# Keyboard_V2.net
KiCad netlist of a schematic drawn in EasyEDA
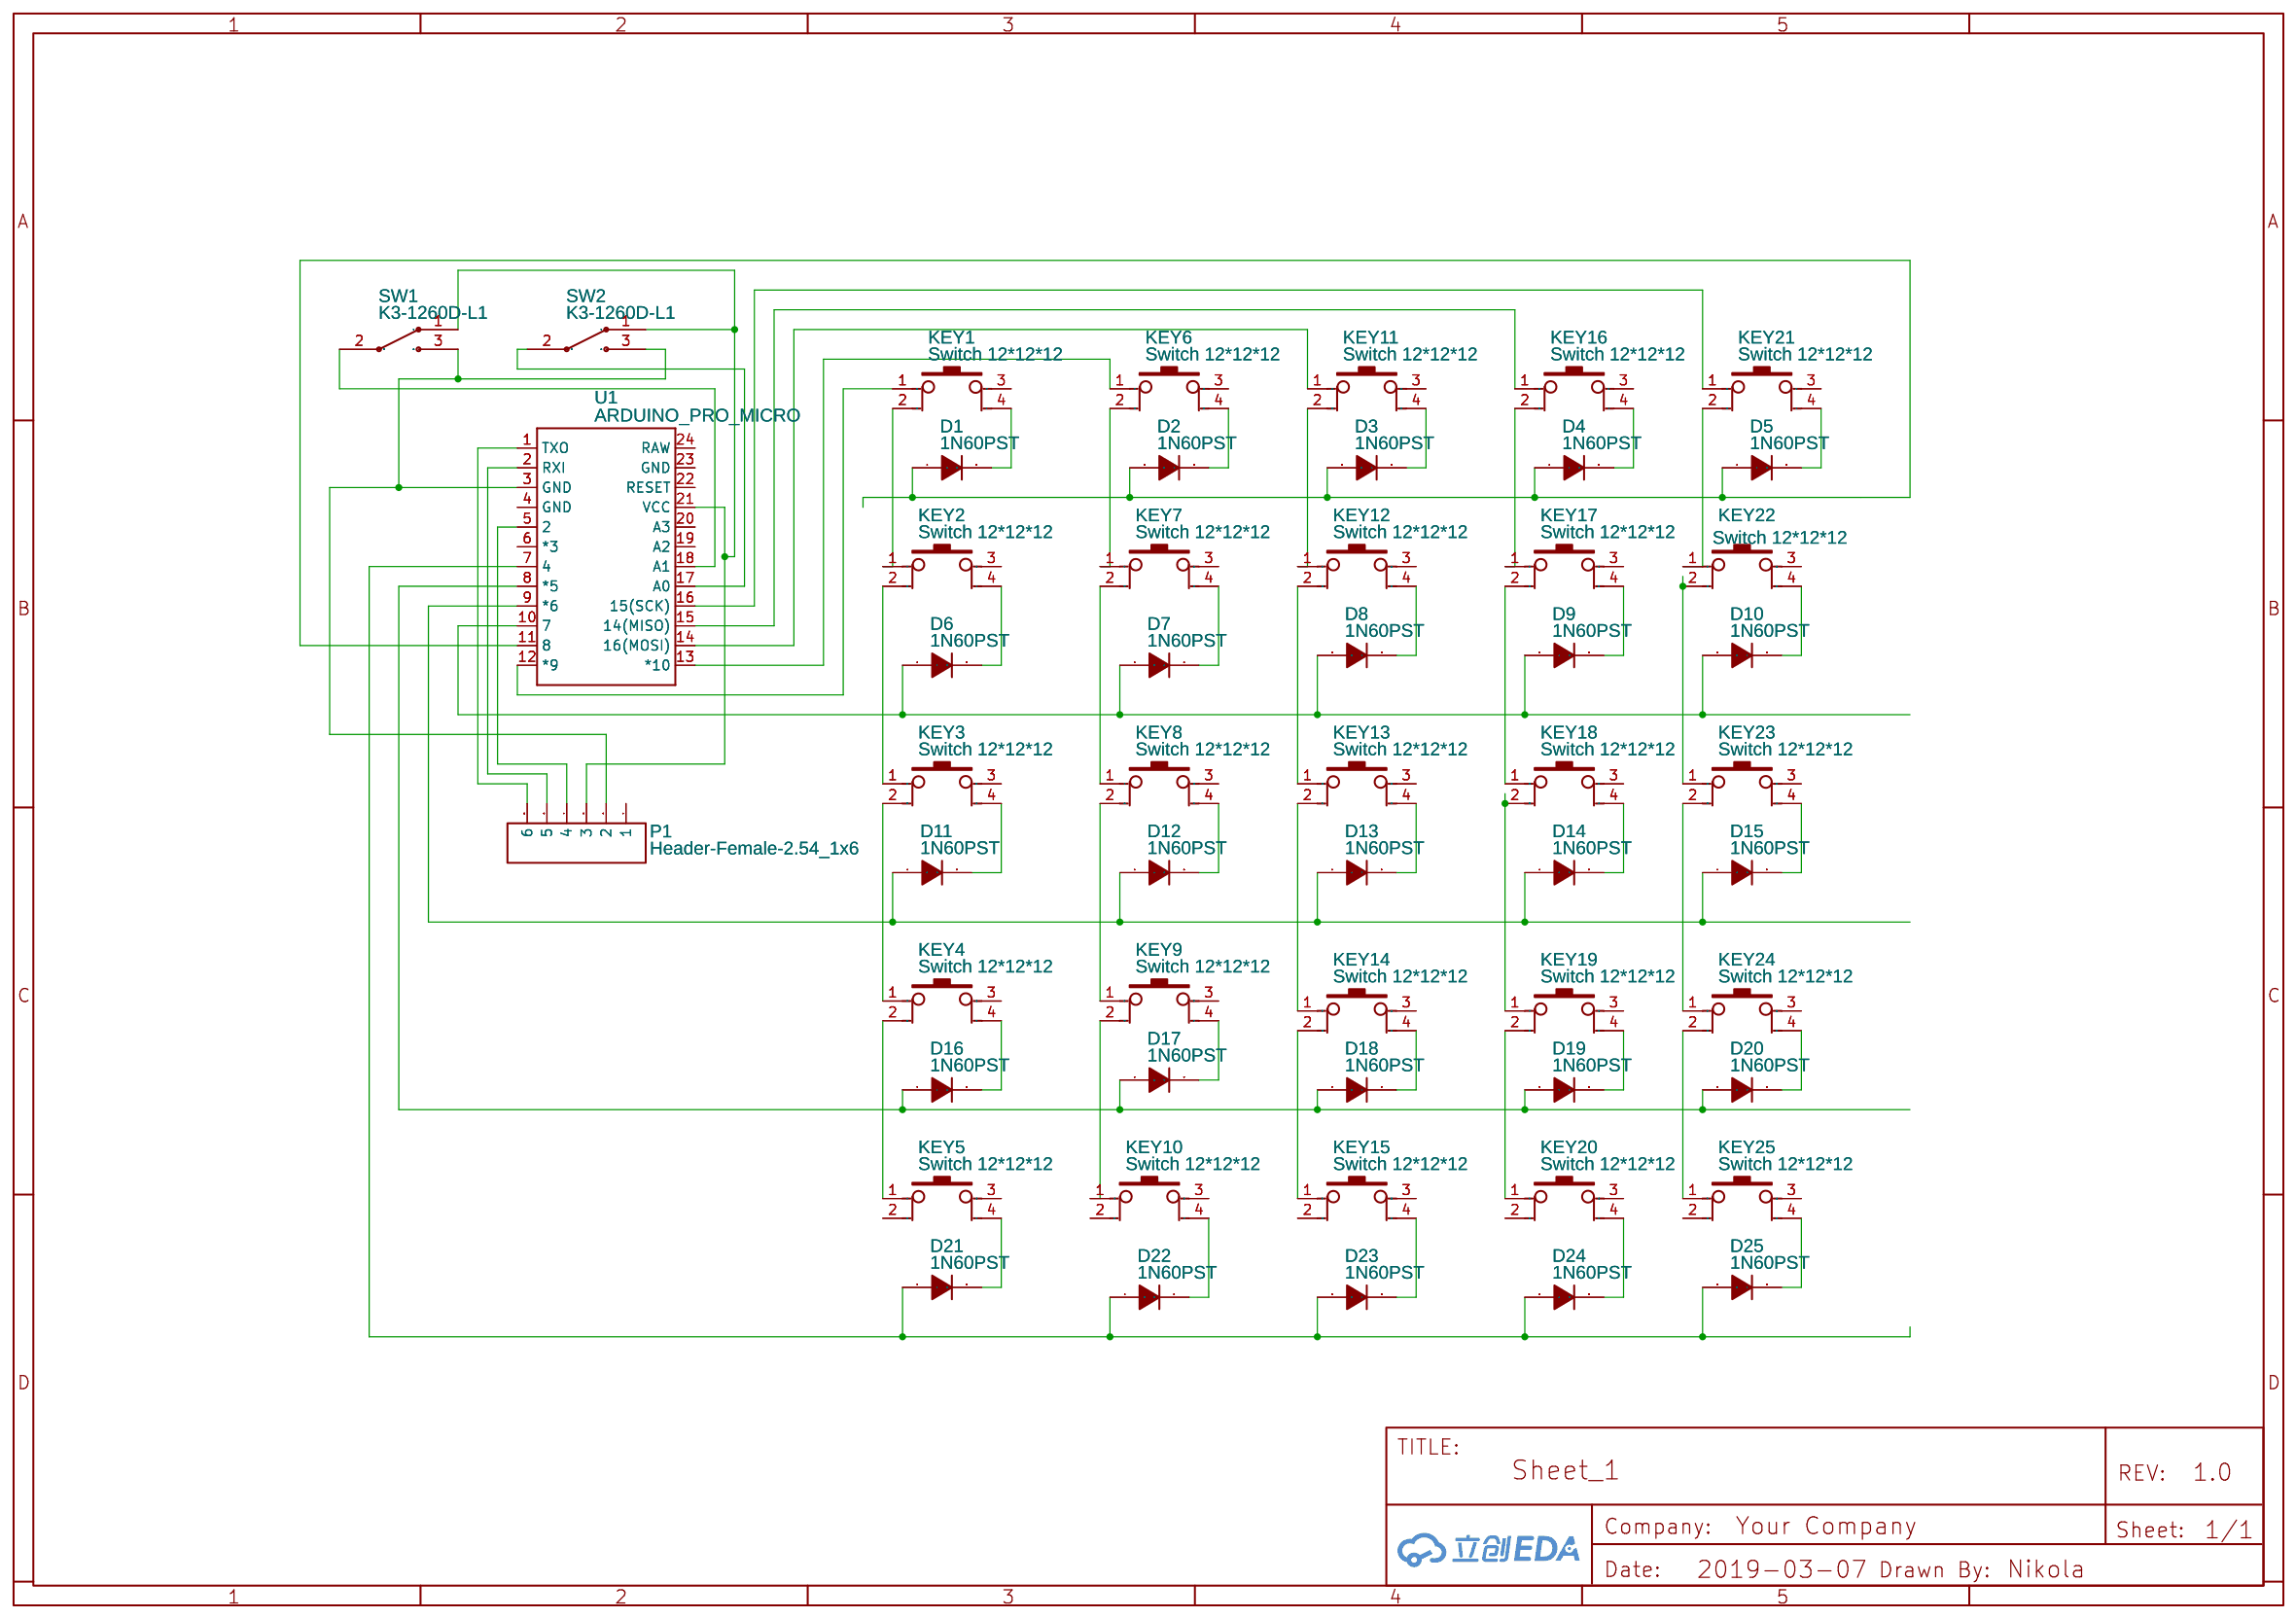
[diagram p0: schematic sheet]

(export (version "E")
  (design (tool "Eeschema 10.0.6"))
  (components
    (comp (ref "D1")
      (value "1N60PST")
      (fields (field (name "BOM_Supplier Part") "C41623"))
      (libsource (lib "") (part "Unknown_475_230"))
    )
    (comp (ref "D2")
      (value "1N60PST")
      (fields (field (name "BOM_Supplier Part") "C41623"))
      (libsource (lib "") (part "Unknown_585_230"))
    )
    (comp (ref "D3")
      (value "1N60PST")
      (fields (field (name "BOM_Supplier Part") "C41623"))
      (libsource (lib "") (part "Unknown_685_230"))
    )
    (comp (ref "D4")
      (value "1N60PST")
      (fields (field (name "BOM_Supplier Part") "C41623"))
      (libsource (lib "") (part "Unknown_790_230"))
    )
    (comp (ref "D5")
      (value "1N60PST")
      (fields (field (name "BOM_Supplier Part") "C41623"))
      (libsource (lib "") (part "Unknown_885_230"))
    )
    (comp (ref "D6")
      (value "1N60PST")
      (fields (field (name "BOM_Supplier Part") "C41623"))
      (libsource (lib "") (part "Unknown_470_330"))
    )
    (comp (ref "D7")
      (value "1N60PST")
      (fields (field (name "BOM_Supplier Part") "C41623"))
      (libsource (lib "") (part "Unknown_580_330"))
    )
    (comp (ref "D8")
      (value "1N60PST")
      (fields (field (name "BOM_Supplier Part") "C41623"))
      (libsource (lib "") (part "Unknown_680_325"))
    )
    (comp (ref "D9")
      (value "1N60PST")
      (fields (field (name "BOM_Supplier Part") "C41623"))
      (libsource (lib "") (part "Unknown_785_325"))
    )
    (comp (ref "D10")
      (value "1N60PST")
      (fields (field (name "BOM_Supplier Part") "C41623"))
      (libsource (lib "") (part "Unknown_875_325"))
    )
    (comp (ref "D11")
      (value "1N60PST")
      (fields (field (name "BOM_Supplier Part") "C41623"))
      (libsource (lib "") (part "Unknown_465_435"))
    )
    (comp (ref "D12")
      (value "1N60PST")
      (fields (field (name "BOM_Supplier Part") "C41623"))
      (libsource (lib "") (part "Unknown_580_435"))
    )
    (comp (ref "D13")
      (value "1N60PST")
      (fields (field (name "BOM_Supplier Part") "C41623"))
      (libsource (lib "") (part "Unknown_680_435"))
    )
    (comp (ref "D14")
      (value "1N60PST")
      (fields (field (name "BOM_Supplier Part") "C41623"))
      (libsource (lib "") (part "Unknown_785_435"))
    )
    (comp (ref "D15")
      (value "1N60PST")
      (fields (field (name "BOM_Supplier Part") "C41623"))
      (libsource (lib "") (part "Unknown_875_435"))
    )
    (comp (ref "D16")
      (value "1N60PST")
      (fields (field (name "BOM_Supplier Part") "C41623"))
      (libsource (lib "") (part "Unknown_470_545"))
    )
    (comp (ref "D17")
      (value "1N60PST")
      (fields (field (name "BOM_Supplier Part") "C41623"))
      (libsource (lib "") (part "Unknown_580_540"))
    )
    (comp (ref "D18")
      (value "1N60PST")
      (fields (field (name "BOM_Supplier Part") "C41623"))
      (libsource (lib "") (part "Unknown_680_545"))
    )
    (comp (ref "D19")
      (value "1N60PST")
      (fields (field (name "BOM_Supplier Part") "C41623"))
      (libsource (lib "") (part "Unknown_785_545"))
    )
    (comp (ref "D20")
      (value "1N60PST")
      (fields (field (name "BOM_Supplier Part") "C41623"))
      (libsource (lib "") (part "Unknown_875_545"))
    )
    (comp (ref "D21")
      (value "1N60PST")
      (fields (field (name "BOM_Supplier Part") "C41623"))
      (libsource (lib "") (part "Unknown_470_645"))
    )
    (comp (ref "D22")
      (value "1N60PST")
      (fields (field (name "BOM_Supplier Part") "C41623"))
      (libsource (lib "") (part "Unknown_575_650"))
    )
    (comp (ref "D23")
      (value "1N60PST")
      (fields (field (name "BOM_Supplier Part") "C41623"))
      (libsource (lib "") (part "Unknown_680_650"))
    )
    (comp (ref "D24")
      (value "1N60PST")
      (fields (field (name "BOM_Supplier Part") "C41623"))
      (libsource (lib "") (part "Unknown_785_650"))
    )
    (comp (ref "D25")
      (value "1N60PST")
      (fields (field (name "BOM_Supplier Part") "C41623"))
      (libsource (lib "") (part "Unknown_875_645"))
    )
    (comp (ref "KEY1")
      (value "Switch 12*12*12")
      (fields (field (name "BOM_Supplier Part") "C14121"))
      (libsource (lib "") (part "Unknown_475_190"))
    )
    (comp (ref "KEY2")
      (value "Switch 12*12*12")
      (fields (field (name "BOM_Supplier Part") "C14121"))
      (libsource (lib "") (part "Unknown_470_280"))
    )
    (comp (ref "KEY3")
      (value "Switch 12*12*12")
      (fields (field (name "BOM_Supplier Part") "C14121"))
      (libsource (lib "") (part "Unknown_470_390"))
    )
    (comp (ref "KEY4")
      (value "Switch 12*12*12")
      (fields (field (name "BOM_Supplier Part") "C14121"))
      (libsource (lib "") (part "Unknown_470_500"))
    )
    (comp (ref "KEY5")
      (value "Switch 12*12*12")
      (fields (field (name "BOM_Supplier Part") "C14121"))
      (libsource (lib "") (part "Unknown_470_600"))
    )
    (comp (ref "KEY6")
      (value "Switch 12*12*12")
      (fields (field (name "BOM_Supplier Part") "C14121"))
      (libsource (lib "") (part "Unknown_585_190"))
    )
    (comp (ref "KEY7")
      (value "Switch 12*12*12")
      (fields (field (name "BOM_Supplier Part") "C14121"))
      (libsource (lib "") (part "Unknown_580_280"))
    )
    (comp (ref "KEY8")
      (value "Switch 12*12*12")
      (fields (field (name "BOM_Supplier Part") "C14121"))
      (libsource (lib "") (part "Unknown_580_390"))
    )
    (comp (ref "KEY9")
      (value "Switch 12*12*12")
      (fields (field (name "BOM_Supplier Part") "C14121"))
      (libsource (lib "") (part "Unknown_580_500"))
    )
    (comp (ref "KEY10")
      (value "Switch 12*12*12")
      (fields (field (name "BOM_Supplier Part") "C14121"))
      (libsource (lib "") (part "Unknown_575_600"))
    )
    (comp (ref "KEY11")
      (value "Switch 12*12*12")
      (fields (field (name "BOM_Supplier Part") "C14121"))
      (libsource (lib "") (part "Unknown_685_190"))
    )
    (comp (ref "KEY12")
      (value "Switch 12*12*12")
      (fields (field (name "BOM_Supplier Part") "C14121"))
      (libsource (lib "") (part "Unknown_680_280"))
    )
    (comp (ref "KEY13")
      (value "Switch 12*12*12")
      (fields (field (name "BOM_Supplier Part") "C14121"))
      (libsource (lib "") (part "Unknown_680_390"))
    )
    (comp (ref "KEY14")
      (value "Switch 12*12*12")
      (fields (field (name "BOM_Supplier Part") "C14121"))
      (libsource (lib "") (part "Unknown_680_505"))
    )
    (comp (ref "KEY15")
      (value "Switch 12*12*12")
      (fields (field (name "BOM_Supplier Part") "C14121"))
      (libsource (lib "") (part "Unknown_680_600"))
    )
    (comp (ref "KEY16")
      (value "Switch 12*12*12")
      (fields (field (name "BOM_Supplier Part") "C14121"))
      (libsource (lib "") (part "Unknown_790_190"))
    )
    (comp (ref "KEY17")
      (value "Switch 12*12*12")
      (fields (field (name "BOM_Supplier Part") "C14121"))
      (libsource (lib "") (part "Unknown_785_280"))
    )
    (comp (ref "KEY18")
      (value "Switch 12*12*12")
      (fields (field (name "BOM_Supplier Part") "C14121"))
      (libsource (lib "") (part "Unknown_785_390"))
    )
    (comp (ref "KEY19")
      (value "Switch 12*12*12")
      (fields (field (name "BOM_Supplier Part") "C14121"))
      (libsource (lib "") (part "Unknown_785_505"))
    )
    (comp (ref "KEY20")
      (value "Switch 12*12*12")
      (fields (field (name "BOM_Supplier Part") "C14121"))
      (libsource (lib "") (part "Unknown_785_600"))
    )
    (comp (ref "KEY21")
      (value "Switch 12*12*12")
      (fields (field (name "BOM_Supplier Part") "C14121"))
      (libsource (lib "") (part "Unknown_885_190"))
    )
    (comp (ref "KEY22")
      (value "Switch 12*12*12")
      (fields (field (name "BOM_Supplier Part") "C14121"))
      (libsource (lib "") (part "Unknown_875_280"))
    )
    (comp (ref "KEY23")
      (value "Switch 12*12*12")
      (fields (field (name "BOM_Supplier Part") "C14121"))
      (libsource (lib "") (part "Unknown_875_390"))
    )
    (comp (ref "KEY24")
      (value "Switch 12*12*12")
      (fields (field (name "BOM_Supplier Part") "C14121"))
      (libsource (lib "") (part "Unknown_875_505"))
    )
    (comp (ref "KEY25")
      (value "Switch 12*12*12")
      (fields (field (name "BOM_Supplier Part") "C14121"))
      (libsource (lib "") (part "Unknown_875_600"))
    )
    (comp (ref "P1")
      (value "Header-Female-2.54_1x6")
      (fields
        (field (name "BOM_Manufacturer Part") "Female header 1*6p")
        (field (name "BOM_Supplier Part") "C40877")
      )
      (libsource (lib "") (part "Unknown_285_415"))
    )
    (comp (ref "SW1")
      (value "K3-1260D-L1")
      (fields (field (name "BOM_Supplier Part") "C92657"))
      (libsource (lib "") (part "Unknown_195_160"))
    )
    (comp (ref "SW2")
      (value "K3-1260D-L1")
      (fields (field (name "BOM_Supplier Part") "C92657"))
      (libsource (lib "") (part "Unknown_290_160"))
    )
    (comp (ref "U1")
      (value "ARDUINO_PRO_MICRO")
      (fields (field (name "BOM_Manufacturer Part") "?"))
      (libsource (lib "") (part "Unknown_300_275"))
    )
  )
  (nets
    (net (code "1") (name "Net-(D1-A)") (class "Default")
      (node (ref "D1") (pin "1") (pinfunction "A_1") (pintype "unspecified"))
      (node (ref "D2") (pin "1") (pinfunction "A_1") (pintype "unspecified"))
      (node (ref "D3") (pin "1") (pinfunction "A_1") (pintype "unspecified"))
      (node (ref "D4") (pin "1") (pinfunction "A_1") (pintype "unspecified"))
      (node (ref "D5") (pin "1") (pinfunction "A_1") (pintype "unspecified"))
      (node (ref "U1") (pin "11") (pinfunction "8_11") (pintype "unspecified"))
    )
    (net (code "2") (name "Net-(D1-K)") (class "Default")
      (node (ref "D1") (pin "2") (pinfunction "K_2") (pintype "unspecified"))
      (node (ref "KEY1") (pin "4") (pinfunction "4_4") (pintype "input"))
    )
    (net (code "3") (name "Net-(D2-K)") (class "Default")
      (node (ref "D2") (pin "2") (pinfunction "K_2") (pintype "unspecified"))
      (node (ref "KEY6") (pin "4") (pinfunction "4_4") (pintype "input"))
    )
    (net (code "4") (name "Net-(D3-K)") (class "Default")
      (node (ref "D3") (pin "2") (pinfunction "K_2") (pintype "unspecified"))
      (node (ref "KEY11") (pin "4") (pinfunction "4_4") (pintype "input"))
    )
    (net (code "5") (name "Net-(D4-K)") (class "Default")
      (node (ref "D4") (pin "2") (pinfunction "K_2") (pintype "unspecified"))
      (node (ref "KEY16") (pin "4") (pinfunction "4_4") (pintype "input"))
    )
    (net (code "6") (name "Net-(D5-K)") (class "Default")
      (node (ref "D5") (pin "2") (pinfunction "K_2") (pintype "unspecified"))
      (node (ref "KEY21") (pin "4") (pinfunction "4_4") (pintype "input"))
    )
    (net (code "7") (name "Net-(D6-K)") (class "Default")
      (node (ref "D6") (pin "2") (pinfunction "K_2") (pintype "unspecified"))
      (node (ref "KEY2") (pin "4") (pinfunction "4_4") (pintype "input"))
    )
    (net (code "8") (name "Net-(D7-K)") (class "Default")
      (node (ref "D7") (pin "2") (pinfunction "K_2") (pintype "unspecified"))
      (node (ref "KEY7") (pin "4") (pinfunction "4_4") (pintype "input"))
    )
    (net (code "9") (name "Net-(D8-K)") (class "Default")
      (node (ref "D8") (pin "2") (pinfunction "K_2") (pintype "unspecified"))
      (node (ref "KEY12") (pin "4") (pinfunction "4_4") (pintype "input"))
    )
    (net (code "10") (name "Net-(D9-K)") (class "Default")
      (node (ref "D9") (pin "2") (pinfunction "K_2") (pintype "unspecified"))
      (node (ref "KEY17") (pin "4") (pinfunction "4_4") (pintype "input"))
    )
    (net (code "11") (name "Net-(D10-A)") (class "Default")
      (node (ref "D10") (pin "1") (pinfunction "A_1") (pintype "unspecified"))
      (node (ref "D6") (pin "1") (pinfunction "A_1") (pintype "unspecified"))
      (node (ref "D7") (pin "1") (pinfunction "A_1") (pintype "unspecified"))
      (node (ref "D8") (pin "1") (pinfunction "A_1") (pintype "unspecified"))
      (node (ref "D9") (pin "1") (pinfunction "A_1") (pintype "unspecified"))
      (node (ref "U1") (pin "10") (pinfunction "7_10") (pintype "unspecified"))
    )
    (net (code "12") (name "Net-(D10-K)") (class "Default")
      (node (ref "D10") (pin "2") (pinfunction "K_2") (pintype "unspecified"))
      (node (ref "KEY22") (pin "4") (pinfunction "4_4") (pintype "input"))
    )
    (net (code "13") (name "Net-(D11-A)") (class "Default")
      (node (ref "D11") (pin "1") (pinfunction "A_1") (pintype "unspecified"))
      (node (ref "D12") (pin "1") (pinfunction "A_1") (pintype "unspecified"))
      (node (ref "D13") (pin "1") (pinfunction "A_1") (pintype "unspecified"))
      (node (ref "D14") (pin "1") (pinfunction "A_1") (pintype "unspecified"))
      (node (ref "D15") (pin "1") (pinfunction "A_1") (pintype "unspecified"))
      (node (ref "U1") (pin "9") (pinfunction "*6_9") (pintype "unspecified"))
    )
    (net (code "14") (name "Net-(D11-K)") (class "Default")
      (node (ref "D11") (pin "2") (pinfunction "K_2") (pintype "unspecified"))
      (node (ref "KEY3") (pin "4") (pinfunction "4_4") (pintype "input"))
    )
    (net (code "15") (name "Net-(D12-K)") (class "Default")
      (node (ref "D12") (pin "2") (pinfunction "K_2") (pintype "unspecified"))
      (node (ref "KEY8") (pin "4") (pinfunction "4_4") (pintype "input"))
    )
    (net (code "16") (name "Net-(D13-K)") (class "Default")
      (node (ref "D13") (pin "2") (pinfunction "K_2") (pintype "unspecified"))
      (node (ref "KEY13") (pin "4") (pinfunction "4_4") (pintype "input"))
    )
    (net (code "17") (name "Net-(D14-K)") (class "Default")
      (node (ref "D14") (pin "2") (pinfunction "K_2") (pintype "unspecified"))
      (node (ref "KEY18") (pin "4") (pinfunction "4_4") (pintype "input"))
    )
    (net (code "18") (name "Net-(D15-K)") (class "Default")
      (node (ref "D15") (pin "2") (pinfunction "K_2") (pintype "unspecified"))
      (node (ref "KEY23") (pin "4") (pinfunction "4_4") (pintype "input"))
    )
    (net (code "19") (name "Net-(D16-A)") (class "Default")
      (node (ref "D16") (pin "1") (pinfunction "A_1") (pintype "unspecified"))
      (node (ref "D17") (pin "1") (pinfunction "A_1") (pintype "unspecified"))
      (node (ref "D18") (pin "1") (pinfunction "A_1") (pintype "unspecified"))
      (node (ref "D19") (pin "1") (pinfunction "A_1") (pintype "unspecified"))
      (node (ref "D20") (pin "1") (pinfunction "A_1") (pintype "unspecified"))
      (node (ref "U1") (pin "8") (pinfunction "*5_8") (pintype "unspecified"))
    )
    (net (code "20") (name "Net-(D16-K)") (class "Default")
      (node (ref "D16") (pin "2") (pinfunction "K_2") (pintype "unspecified"))
      (node (ref "KEY4") (pin "4") (pinfunction "4_4") (pintype "input"))
    )
    (net (code "21") (name "Net-(D17-K)") (class "Default")
      (node (ref "D17") (pin "2") (pinfunction "K_2") (pintype "unspecified"))
      (node (ref "KEY9") (pin "4") (pinfunction "4_4") (pintype "input"))
    )
    (net (code "22") (name "Net-(D18-K)") (class "Default")
      (node (ref "D18") (pin "2") (pinfunction "K_2") (pintype "unspecified"))
      (node (ref "KEY14") (pin "4") (pinfunction "4_4") (pintype "input"))
    )
    (net (code "23") (name "Net-(D19-K)") (class "Default")
      (node (ref "D19") (pin "2") (pinfunction "K_2") (pintype "unspecified"))
      (node (ref "KEY19") (pin "4") (pinfunction "4_4") (pintype "input"))
    )
    (net (code "24") (name "Net-(D20-K)") (class "Default")
      (node (ref "D20") (pin "2") (pinfunction "K_2") (pintype "unspecified"))
      (node (ref "KEY24") (pin "4") (pinfunction "4_4") (pintype "input"))
    )
    (net (code "25") (name "Net-(D21-A)") (class "Default")
      (node (ref "D21") (pin "1") (pinfunction "A_1") (pintype "unspecified"))
      (node (ref "D22") (pin "1") (pinfunction "A_1") (pintype "unspecified"))
      (node (ref "D23") (pin "1") (pinfunction "A_1") (pintype "unspecified"))
      (node (ref "D24") (pin "1") (pinfunction "A_1") (pintype "unspecified"))
      (node (ref "D25") (pin "1") (pinfunction "A_1") (pintype "unspecified"))
      (node (ref "U1") (pin "7") (pinfunction "4_7") (pintype "unspecified"))
    )
    (net (code "26") (name "Net-(D21-K)") (class "Default")
      (node (ref "D21") (pin "2") (pinfunction "K_2") (pintype "unspecified"))
      (node (ref "KEY5") (pin "4") (pinfunction "4_4") (pintype "input"))
    )
    (net (code "27") (name "Net-(D22-K)") (class "Default")
      (node (ref "D22") (pin "2") (pinfunction "K_2") (pintype "unspecified"))
      (node (ref "KEY10") (pin "4") (pinfunction "4_4") (pintype "input"))
    )
    (net (code "28") (name "Net-(D23-K)") (class "Default")
      (node (ref "D23") (pin "2") (pinfunction "K_2") (pintype "unspecified"))
      (node (ref "KEY15") (pin "4") (pinfunction "4_4") (pintype "input"))
    )
    (net (code "29") (name "Net-(D24-K)") (class "Default")
      (node (ref "D24") (pin "2") (pinfunction "K_2") (pintype "unspecified"))
      (node (ref "KEY20") (pin "4") (pinfunction "4_4") (pintype "input"))
    )
    (net (code "30") (name "Net-(D25-K)") (class "Default")
      (node (ref "D25") (pin "2") (pinfunction "K_2") (pintype "unspecified"))
      (node (ref "KEY25") (pin "4") (pinfunction "4_4") (pintype "input"))
    )
    (net (code "31") (name "Net-(KEY1-Pad2)") (class "Default")
      (node (ref "KEY1") (pin "2") (pinfunction "2_2") (pintype "input"))
      (node (ref "KEY2") (pin "1") (pinfunction "1_1") (pintype "input"))
    )
    (net (code "32") (name "Net-(KEY2-Pad2)") (class "Default")
      (node (ref "KEY2") (pin "2") (pinfunction "2_2") (pintype "input"))
      (node (ref "KEY3") (pin "1") (pinfunction "1_1") (pintype "input"))
    )
    (net (code "33") (name "Net-(KEY3-Pad2)") (class "Default")
      (node (ref "KEY3") (pin "2") (pinfunction "2_2") (pintype "input"))
      (node (ref "KEY4") (pin "1") (pinfunction "1_1") (pintype "input"))
    )
    (net (code "34") (name "Net-(KEY4-Pad2)") (class "Default")
      (node (ref "KEY4") (pin "2") (pinfunction "2_2") (pintype "input"))
      (node (ref "KEY5") (pin "1") (pinfunction "1_1") (pintype "input"))
    )
    (net (code "35") (name "Net-(KEY6-Pad2)") (class "Default")
      (node (ref "KEY6") (pin "2") (pinfunction "2_2") (pintype "input"))
      (node (ref "KEY7") (pin "1") (pinfunction "1_1") (pintype "input"))
    )
    (net (code "36") (name "Net-(KEY7-Pad2)") (class "Default")
      (node (ref "KEY7") (pin "2") (pinfunction "2_2") (pintype "input"))
      (node (ref "KEY8") (pin "1") (pinfunction "1_1") (pintype "input"))
    )
    (net (code "37") (name "Net-(KEY8-Pad2)") (class "Default")
      (node (ref "KEY8") (pin "2") (pinfunction "2_2") (pintype "input"))
      (node (ref "KEY9") (pin "1") (pinfunction "1_1") (pintype "input"))
    )
    (net (code "38") (name "Net-(KEY10-Pad1)") (class "Default")
      (node (ref "KEY10") (pin "1") (pinfunction "1_1") (pintype "input"))
      (node (ref "KEY9") (pin "2") (pinfunction "2_2") (pintype "input"))
    )
    (net (code "39") (name "Net-(KEY11-Pad2)") (class "Default")
      (node (ref "KEY11") (pin "2") (pinfunction "2_2") (pintype "input"))
      (node (ref "KEY12") (pin "1") (pinfunction "1_1") (pintype "input"))
    )
    (net (code "40") (name "Net-(KEY12-Pad2)") (class "Default")
      (node (ref "KEY12") (pin "2") (pinfunction "2_2") (pintype "input"))
      (node (ref "KEY13") (pin "1") (pinfunction "1_1") (pintype "input"))
    )
    (net (code "41") (name "Net-(KEY13-Pad2)") (class "Default")
      (node (ref "KEY13") (pin "2") (pinfunction "2_2") (pintype "input"))
      (node (ref "KEY14") (pin "1") (pinfunction "1_1") (pintype "input"))
    )
    (net (code "42") (name "Net-(KEY14-Pad2)") (class "Default")
      (node (ref "KEY14") (pin "2") (pinfunction "2_2") (pintype "input"))
      (node (ref "KEY15") (pin "1") (pinfunction "1_1") (pintype "input"))
    )
    (net (code "43") (name "Net-(KEY16-Pad2)") (class "Default")
      (node (ref "KEY16") (pin "2") (pinfunction "2_2") (pintype "input"))
      (node (ref "KEY17") (pin "1") (pinfunction "1_1") (pintype "input"))
    )
    (net (code "44") (name "Net-(KEY17-Pad2)") (class "Default")
      (node (ref "KEY17") (pin "2") (pinfunction "2_2") (pintype "input"))
      (node (ref "KEY18") (pin "1") (pinfunction "1_1") (pintype "input"))
    )
    (net (code "45") (name "Net-(KEY18-Pad2)") (class "Default")
      (node (ref "KEY18") (pin "2") (pinfunction "2_2") (pintype "input"))
      (node (ref "KEY19") (pin "1") (pinfunction "1_1") (pintype "input"))
    )
    (net (code "46") (name "Net-(KEY19-Pad2)") (class "Default")
      (node (ref "KEY19") (pin "2") (pinfunction "2_2") (pintype "input"))
      (node (ref "KEY20") (pin "1") (pinfunction "1_1") (pintype "input"))
    )
    (net (code "47") (name "Net-(KEY21-Pad2)") (class "Default")
      (node (ref "KEY21") (pin "2") (pinfunction "2_2") (pintype "input"))
      (node (ref "KEY22") (pin "1") (pinfunction "1_1") (pintype "input"))
    )
    (net (code "48") (name "Net-(KEY22-Pad2)") (class "Default")
      (node (ref "KEY22") (pin "2") (pinfunction "2_2") (pintype "input"))
      (node (ref "KEY23") (pin "1") (pinfunction "1_1") (pintype "input"))
    )
    (net (code "49") (name "Net-(KEY23-Pad2)") (class "Default")
      (node (ref "KEY23") (pin "2") (pinfunction "2_2") (pintype "input"))
      (node (ref "KEY24") (pin "1") (pinfunction "1_1") (pintype "input"))
    )
    (net (code "50") (name "Net-(KEY24-Pad2)") (class "Default")
      (node (ref "KEY24") (pin "2") (pinfunction "2_2") (pintype "input"))
      (node (ref "KEY25") (pin "1") (pinfunction "1_1") (pintype "input"))
    )
    (net (code "51") (name "Net-(P1-Pad2)") (class "Default")
      (node (ref "P1") (pin "2") (pinfunction "2_2") (pintype "input"))
      (node (ref "SW1") (pin "3") (pinfunction "3_3") (pintype "unspecified"))
      (node (ref "SW2") (pin "3") (pinfunction "3_3") (pintype "unspecified"))
      (node (ref "U1") (pin "3") (pinfunction "GND_3") (pintype "unspecified"))
    )
    (net (code "52") (name "Net-(U1-*9)") (class "Default")
      (node (ref "KEY1") (pin "1") (pinfunction "1_1") (pintype "input"))
      (node (ref "U1") (pin "12") (pinfunction "*9_12") (pintype "unspecified"))
    )
    (net (code "53") (name "Net-(U1-*10)") (class "Default")
      (node (ref "KEY6") (pin "1") (pinfunction "1_1") (pintype "input"))
      (node (ref "U1") (pin "13") (pinfunction "*10_13") (pintype "unspecified"))
    )
    (net (code "54") (name "Net-(U1-2)") (class "Default")
      (node (ref "P1") (pin "4") (pinfunction "4_4") (pintype "input"))
      (node (ref "U1") (pin "5") (pinfunction "2_5") (pintype "unspecified"))
    )
    (net (code "55") (name "Net-(U1-14(MISO))") (class "Default")
      (node (ref "KEY16") (pin "1") (pinfunction "1_1") (pintype "input"))
      (node (ref "U1") (pin "15") (pinfunction "14(MISO)_15") (pintype "unspecified"))
    )
    (net (code "56") (name "Net-(U1-15(SCK))") (class "Default")
      (node (ref "KEY21") (pin "1") (pinfunction "1_1") (pintype "input"))
      (node (ref "U1") (pin "16") (pinfunction "15(SCK)_16") (pintype "unspecified"))
    )
    (net (code "57") (name "Net-(U1-16(MOSI))") (class "Default")
      (node (ref "KEY11") (pin "1") (pinfunction "1_1") (pintype "input"))
      (node (ref "U1") (pin "14") (pinfunction "16(MOSI)_14") (pintype "unspecified"))
    )
    (net (code "58") (name "Net-(U1-A0)") (class "Default")
      (node (ref "SW2") (pin "2") (pinfunction "2_2") (pintype "unspecified"))
      (node (ref "U1") (pin "17") (pinfunction "A0_17") (pintype "unspecified"))
    )
    (net (code "59") (name "Net-(U1-A1)") (class "Default")
      (node (ref "SW1") (pin "2") (pinfunction "2_2") (pintype "unspecified"))
      (node (ref "U1") (pin "18") (pinfunction "A1_18") (pintype "unspecified"))
    )
    (net (code "60") (name "Net-(U1-RXI)") (class "Default")
      (node (ref "P1") (pin "5") (pinfunction "5_5") (pintype "input"))
      (node (ref "U1") (pin "2") (pinfunction "RXI_2") (pintype "unspecified"))
    )
    (net (code "61") (name "Net-(U1-TXO)") (class "Default")
      (node (ref "P1") (pin "6") (pinfunction "6_6") (pintype "input"))
      (node (ref "U1") (pin "1") (pinfunction "TXO_1") (pintype "unspecified"))
    )
    (net (code "62") (name "Net-(U1-VCC)") (class "Default")
      (node (ref "P1") (pin "3") (pinfunction "3_3") (pintype "input"))
      (node (ref "SW1") (pin "1") (pinfunction "1_1") (pintype "unspecified"))
      (node (ref "SW2") (pin "1") (pinfunction "1_1") (pintype "unspecified"))
      (node (ref "U1") (pin "21") (pinfunction "VCC_21") (pintype "unspecified"))
    )
    (net (code "63") (name "unconnected-(KEY1-Pad3)") (class "Default")
      (node (ref "KEY1") (pin "3") (pinfunction "3_3") (pintype "input"))
    )
    (net (code "64") (name "unconnected-(KEY2-Pad3)") (class "Default")
      (node (ref "KEY2") (pin "3") (pinfunction "3_3") (pintype "input"))
    )
    (net (code "65") (name "unconnected-(KEY3-Pad3)") (class "Default")
      (node (ref "KEY3") (pin "3") (pinfunction "3_3") (pintype "input"))
    )
    (net (code "66") (name "unconnected-(KEY4-Pad3)") (class "Default")
      (node (ref "KEY4") (pin "3") (pinfunction "3_3") (pintype "input"))
    )
    (net (code "67") (name "unconnected-(KEY5-Pad2)") (class "Default")
      (node (ref "KEY5") (pin "2") (pinfunction "2_2") (pintype "input"))
    )
    (net (code "68") (name "unconnected-(KEY5-Pad3)") (class "Default")
      (node (ref "KEY5") (pin "3") (pinfunction "3_3") (pintype "input"))
    )
    (net (code "69") (name "unconnected-(KEY6-Pad3)") (class "Default")
      (node (ref "KEY6") (pin "3") (pinfunction "3_3") (pintype "input"))
    )
    (net (code "70") (name "unconnected-(KEY7-Pad3)") (class "Default")
      (node (ref "KEY7") (pin "3") (pinfunction "3_3") (pintype "input"))
    )
    (net (code "71") (name "unconnected-(KEY8-Pad3)") (class "Default")
      (node (ref "KEY8") (pin "3") (pinfunction "3_3") (pintype "input"))
    )
    (net (code "72") (name "unconnected-(KEY9-Pad3)") (class "Default")
      (node (ref "KEY9") (pin "3") (pinfunction "3_3") (pintype "input"))
    )
    (net (code "73") (name "unconnected-(KEY10-Pad2)") (class "Default")
      (node (ref "KEY10") (pin "2") (pinfunction "2_2") (pintype "input"))
    )
    (net (code "74") (name "unconnected-(KEY10-Pad3)") (class "Default")
      (node (ref "KEY10") (pin "3") (pinfunction "3_3") (pintype "input"))
    )
    (net (code "75") (name "unconnected-(KEY11-Pad3)") (class "Default")
      (node (ref "KEY11") (pin "3") (pinfunction "3_3") (pintype "input"))
    )
    (net (code "76") (name "unconnected-(KEY12-Pad3)") (class "Default")
      (node (ref "KEY12") (pin "3") (pinfunction "3_3") (pintype "input"))
    )
    (net (code "77") (name "unconnected-(KEY13-Pad3)") (class "Default")
      (node (ref "KEY13") (pin "3") (pinfunction "3_3") (pintype "input"))
    )
    (net (code "78") (name "unconnected-(KEY14-Pad3)") (class "Default")
      (node (ref "KEY14") (pin "3") (pinfunction "3_3") (pintype "input"))
    )
    (net (code "79") (name "unconnected-(KEY15-Pad2)") (class "Default")
      (node (ref "KEY15") (pin "2") (pinfunction "2_2") (pintype "input"))
    )
    (net (code "80") (name "unconnected-(KEY15-Pad3)") (class "Default")
      (node (ref "KEY15") (pin "3") (pinfunction "3_3") (pintype "input"))
    )
    (net (code "81") (name "unconnected-(KEY16-Pad3)") (class "Default")
      (node (ref "KEY16") (pin "3") (pinfunction "3_3") (pintype "input"))
    )
    (net (code "82") (name "unconnected-(KEY17-Pad3)") (class "Default")
      (node (ref "KEY17") (pin "3") (pinfunction "3_3") (pintype "input"))
    )
    (net (code "83") (name "unconnected-(KEY18-Pad3)") (class "Default")
      (node (ref "KEY18") (pin "3") (pinfunction "3_3") (pintype "input"))
    )
    (net (code "84") (name "unconnected-(KEY19-Pad3)") (class "Default")
      (node (ref "KEY19") (pin "3") (pinfunction "3_3") (pintype "input"))
    )
    (net (code "85") (name "unconnected-(KEY20-Pad2)") (class "Default")
      (node (ref "KEY20") (pin "2") (pinfunction "2_2") (pintype "input"))
    )
    (net (code "86") (name "unconnected-(KEY20-Pad3)") (class "Default")
      (node (ref "KEY20") (pin "3") (pinfunction "3_3") (pintype "input"))
    )
    (net (code "87") (name "unconnected-(KEY21-Pad3)") (class "Default")
      (node (ref "KEY21") (pin "3") (pinfunction "3_3") (pintype "input"))
    )
    (net (code "88") (name "unconnected-(KEY22-Pad3)") (class "Default")
      (node (ref "KEY22") (pin "3") (pinfunction "3_3") (pintype "input"))
    )
    (net (code "89") (name "unconnected-(KEY23-Pad3)") (class "Default")
      (node (ref "KEY23") (pin "3") (pinfunction "3_3") (pintype "input"))
    )
    (net (code "90") (name "unconnected-(KEY24-Pad3)") (class "Default")
      (node (ref "KEY24") (pin "3") (pinfunction "3_3") (pintype "input"))
    )
    (net (code "91") (name "unconnected-(KEY25-Pad2)") (class "Default")
      (node (ref "KEY25") (pin "2") (pinfunction "2_2") (pintype "input"))
    )
    (net (code "92") (name "unconnected-(KEY25-Pad3)") (class "Default")
      (node (ref "KEY25") (pin "3") (pinfunction "3_3") (pintype "input"))
    )
    (net (code "93") (name "unconnected-(P1-Pad1)") (class "Default")
      (node (ref "P1") (pin "1") (pinfunction "1_1") (pintype "input"))
    )
    (net (code "94") (name "unconnected-(U1-*3-Pad6)") (class "Default")
      (node (ref "U1") (pin "6") (pinfunction "*3_6") (pintype "unspecified"))
    )
    (net (code "95") (name "unconnected-(U1-A2-Pad19)") (class "Default")
      (node (ref "U1") (pin "19") (pinfunction "A2_19") (pintype "unspecified"))
    )
    (net (code "96") (name "unconnected-(U1-A3-Pad20)") (class "Default")
      (node (ref "U1") (pin "20") (pinfunction "A3_20") (pintype "unspecified"))
    )
    (net (code "97") (name "unconnected-(U1-GND-Pad4)") (class "Default")
      (node (ref "U1") (pin "4") (pinfunction "GND_4") (pintype "unspecified"))
    )
    (net (code "98") (name "unconnected-(U1-GND-Pad23)") (class "Default")
      (node (ref "U1") (pin "23") (pinfunction "GND_23") (pintype "unspecified"))
    )
    (net (code "99") (name "unconnected-(U1-RAW-Pad24)") (class "Default")
      (node (ref "U1") (pin "24") (pinfunction "RAW_24") (pintype "unspecified"))
    )
    (net (code "100") (name "unconnected-(U1-RESET-Pad22)") (class "Default")
      (node (ref "U1") (pin "22") (pinfunction "RESET_22") (pintype "unspecified"))
    )
  )
)
